# dustmap_lora.net
KiCad netlist of a schematic drawn in EAGLE
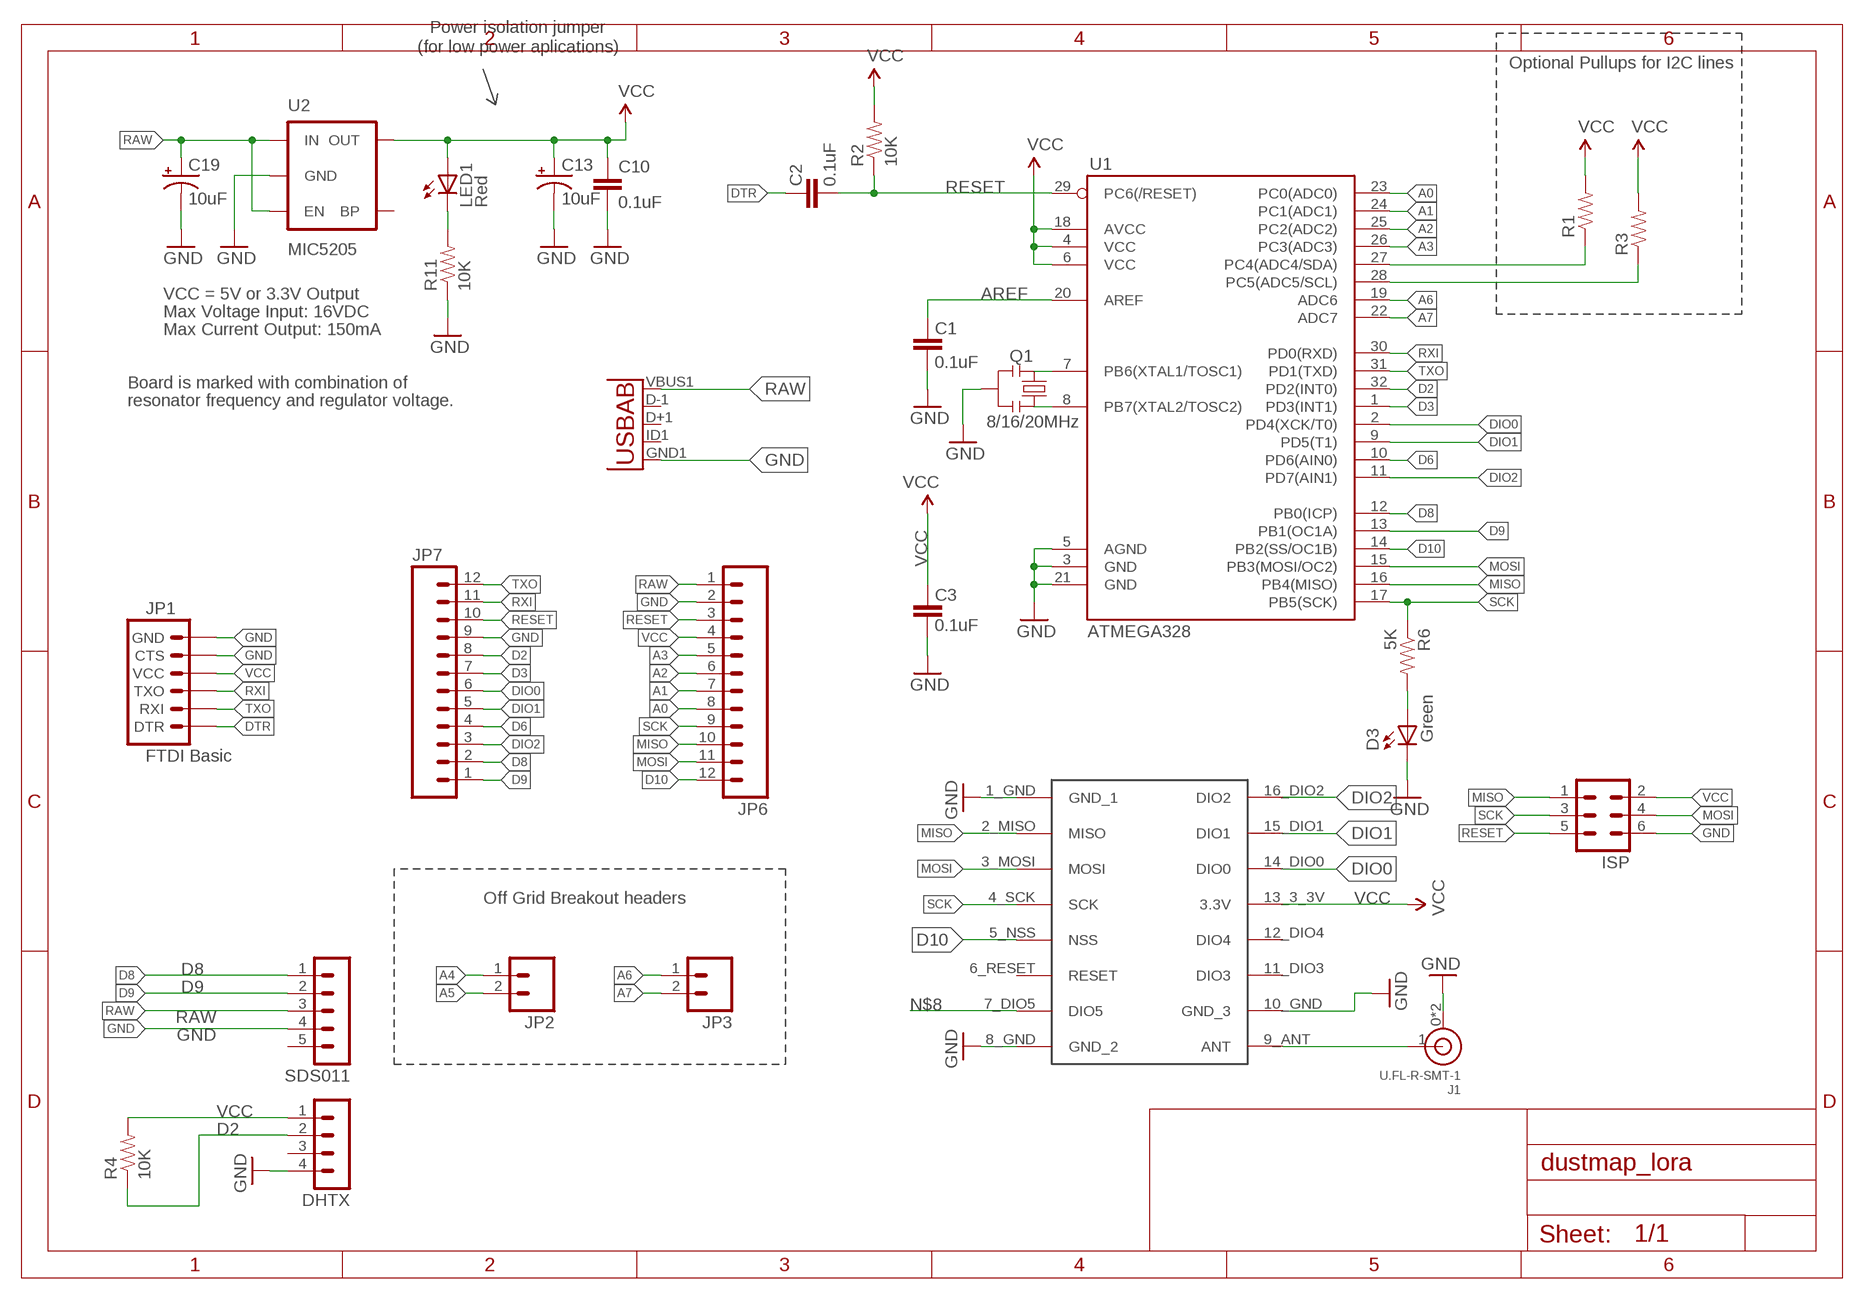
[diagram p0: schematic, sheet 1]

(export (version "E")
  (design (tool "Eeschema 10.0.6"))
  (components
    (comp (ref "C1")
      (value "0.1uF")
      (footprint "eagle-import:0603-CAP")
      (libsource (lib "eagle-import") (part "CAP0603-CAP"))
    )
    (comp (ref "C2")
      (value "0.1uF")
      (footprint "eagle-import:0603-CAP")
      (libsource (lib "eagle-import") (part "CAP0603-CAP"))
    )
    (comp (ref "C3")
      (value "0.1uF")
      (footprint "eagle-import:0603-CAP")
      (libsource (lib "eagle-import") (part "CAP0603-CAP"))
    )
    (comp (ref "C10")
      (value "0.1uF")
      (footprint "eagle-import:0603-CAP")
      (libsource (lib "eagle-import") (part "CAP0603-CAP"))
    )
    (comp (ref "C13")
      (value "10uF")
      (footprint "eagle-import:EIA3216")
      (libsource (lib "eagle-import") (part "CAP_POL1206"))
    )
    (comp (ref "C19")
      (value "10uF")
      (footprint "eagle-import:EIA3216")
      (libsource (lib "eagle-import") (part "CAP_POL1206"))
    )
    (comp (ref "D3")
      (value "Green")
      (footprint "eagle-import:0603-LED-ALT1")
      (libsource (lib "eagle-import") (part "LED"))
    )
    (comp (ref "DHTX")
      (value "MA04-1")
      (footprint "eagle-import:MA04-1")
      (libsource (lib "eagle-import") (part "MA04-1"))
    )
    (comp (ref "ISP")
      (value "MA03-2")
      (footprint "eagle-import:MA03-2")
      (libsource (lib "eagle-import") (part "MA03-2"))
    )
    (comp (ref "J1")
      (value "U.FL-R-SMT-1")
      (footprint "eagle-import:U.FL")
      (libsource (lib "eagle-import") (part "U.FL-R-SMT-1"))
    )
    (comp (ref "JP1")
      (value "FTDI Basic")
      (footprint "eagle-import:1X06")
      (libsource (lib "eagle-import") (part "ARDUINO_SERIAL_PROGRAMPTH"))
    )
    (comp (ref "JP2")
      (value "M02PTH")
      (footprint "eagle-import:1X02")
      (libsource (lib "eagle-import") (part "M02PTH"))
    )
    (comp (ref "JP3")
      (value "M02PTH")
      (footprint "eagle-import:1X02")
      (libsource (lib "eagle-import") (part "M02PTH"))
    )
    (comp (ref "JP6")
      (value "M12PTH")
      (footprint "eagle-import:1X12")
      (libsource (lib "eagle-import") (part "M12PTH"))
    )
    (comp (ref "JP7")
      (value "M12PTH")
      (footprint "eagle-import:1X12")
      (libsource (lib "eagle-import") (part "M12PTH"))
    )
    (comp (ref "LED1")
      (value "Red")
      (footprint "eagle-import:0603-LED-ALT1")
      (libsource (lib "eagle-import") (part "LED"))
    )
    (comp (ref "Q1")
      (value "8/16/20MHz")
      (footprint "eagle-import:RESONATOR-SMD-1_1")
      (libsource (lib "eagle-import") (part "RESONATOR1{colon}1"))
    )
    (comp (ref "R1")
      (value "RESISTOR0603-RES")
      (footprint "eagle-import:0603-RES")
      (libsource (lib "eagle-import") (part "RESISTOR0603-RES"))
    )
    (comp (ref "R2")
      (value "10K")
      (footprint "eagle-import:0603-RES")
      (libsource (lib "eagle-import") (part "RESISTOR0603-RES"))
    )
    (comp (ref "R3")
      (value "RESISTOR0603-RES")
      (footprint "eagle-import:0603-RES")
      (libsource (lib "eagle-import") (part "RESISTOR0603-RES"))
    )
    (comp (ref "R4")
      (value "10K")
      (footprint "eagle-import:0603-RES")
      (libsource (lib "eagle-import") (part "RESISTOR0603-RES"))
    )
    (comp (ref "R6")
      (value "5K")
      (footprint "eagle-import:0603-RES")
      (libsource (lib "eagle-import") (part "RESISTOR0603-RES"))
    )
    (comp (ref "R11")
      (value "10K")
      (footprint "eagle-import:0603-RES")
      (libsource (lib "eagle-import") (part "RESISTOR0603-RES"))
    )
    (comp (ref "SDS011")
      (value "MA05-1")
      (footprint "eagle-import:MA05-1")
      (libsource (lib "eagle-import") (part "MA05-1"))
    )
    (comp (ref "U$1")
      (value "RF96")
      (footprint "eagle-import:SMD")
      (libsource (lib "eagle-import") (part "RF96"))
    )
    (comp (ref "U1")
      (value "ATMEGA328")
      (footprint "eagle-import:TQFP32-08")
      (libsource (lib "eagle-import") (part "ATMEGA168"))
    )
    (comp (ref "U2")
      (value "MIC5205")
      (footprint "eagle-import:SOT23-5")
      (libsource (lib "eagle-import") (part "V_REG_LDOSMD"))
    )
    (comp (ref "U3")
      (value "USB\"\"")
      (footprint "eagle-import:USB-MICRO-SMD")
      (libsource (lib "eagle-import") (part "USB{dblquote}{dblquote}"))
    )
  )
  (nets
    (net (code "1") (name "/AREF") (class "Default")
      (node (ref "C1") (pin "2") (pinfunction "2_2") (pintype "passive"))
      (node (ref "U1") (pin "20") (pinfunction "AREF_20") (pintype "bidirectional"))
    )
    (net (code "2") (name "/N$8") (class "Default")
      (node (ref "U$1") (pin "7_DIO5") (pinfunction "DIO5_7_DIO5") (pintype "bidirectional"))
    )
    (net (code "3") (name "A0") (class "Default")
      (node (ref "JP6") (pin "8") (pinfunction "8_8") (pintype "passive"))
      (node (ref "U1") (pin "23") (pinfunction "PC0(ADC0)_23") (pintype "bidirectional"))
    )
    (net (code "4") (name "A1") (class "Default")
      (node (ref "JP6") (pin "7") (pinfunction "7_7") (pintype "passive"))
      (node (ref "U1") (pin "24") (pinfunction "PC1(ADC1)_24") (pintype "bidirectional"))
    )
    (net (code "5") (name "A2") (class "Default")
      (node (ref "JP6") (pin "6") (pinfunction "6_6") (pintype "passive"))
      (node (ref "U1") (pin "25") (pinfunction "PC2(ADC2)_25") (pintype "bidirectional"))
    )
    (net (code "6") (name "A3") (class "Default")
      (node (ref "JP6") (pin "5") (pinfunction "5_5") (pintype "passive"))
      (node (ref "U1") (pin "26") (pinfunction "PC3(ADC3)_26") (pintype "bidirectional"))
    )
    (net (code "7") (name "A4") (class "Default")
      (node (ref "JP2") (pin "1") (pinfunction "1_1") (pintype "passive"))
      (node (ref "R1") (pin "1") (pinfunction "1_1") (pintype "passive"))
      (node (ref "U1") (pin "27") (pinfunction "PC4(ADC4/SDA)_27") (pintype "bidirectional"))
    )
    (net (code "8") (name "A5") (class "Default")
      (node (ref "JP2") (pin "2") (pinfunction "2_2") (pintype "passive"))
      (node (ref "R3") (pin "1") (pinfunction "1_1") (pintype "passive"))
      (node (ref "U1") (pin "28") (pinfunction "PC5(ADC5/SCL)_28") (pintype "bidirectional"))
    )
    (net (code "9") (name "A6") (class "Default")
      (node (ref "JP3") (pin "1") (pinfunction "1_1") (pintype "passive"))
      (node (ref "U1") (pin "19") (pinfunction "ADC6_19") (pintype "bidirectional"))
    )
    (net (code "10") (name "A7") (class "Default")
      (node (ref "JP3") (pin "2") (pinfunction "2_2") (pintype "passive"))
      (node (ref "U1") (pin "22") (pinfunction "ADC7_22") (pintype "bidirectional"))
    )
    (net (code "11") (name "D2") (class "Default")
      (node (ref "DHTX") (pin "2") (pinfunction "2_2") (pintype "passive"))
      (node (ref "JP7") (pin "8") (pinfunction "8_8") (pintype "passive"))
      (node (ref "R4") (pin "1") (pinfunction "1_1") (pintype "passive"))
      (node (ref "U1") (pin "32") (pinfunction "PD2(INT0)_32") (pintype "bidirectional"))
    )
    (net (code "12") (name "D3") (class "Default")
      (node (ref "JP7") (pin "7") (pinfunction "7_7") (pintype "passive"))
      (node (ref "U1") (pin "1") (pinfunction "PD3(INT1)_1") (pintype "bidirectional"))
    )
    (net (code "13") (name "D6") (class "Default")
      (node (ref "JP7") (pin "4") (pinfunction "4_4") (pintype "passive"))
      (node (ref "U1") (pin "10") (pinfunction "PD6(AIN0)_10") (pintype "bidirectional"))
    )
    (net (code "14") (name "D8") (class "Default")
      (node (ref "JP7") (pin "2") (pinfunction "2_2") (pintype "passive"))
      (node (ref "SDS011") (pin "1") (pinfunction "1_1") (pintype "passive"))
      (node (ref "U1") (pin "12") (pinfunction "PB0(ICP)_12") (pintype "bidirectional"))
    )
    (net (code "15") (name "D9") (class "Default")
      (node (ref "JP7") (pin "1") (pinfunction "1_1") (pintype "passive"))
      (node (ref "SDS011") (pin "2") (pinfunction "2_2") (pintype "passive"))
      (node (ref "U1") (pin "13") (pinfunction "PB1(OC1A)_13") (pintype "bidirectional"))
    )
    (net (code "16") (name "D10") (class "Default")
      (node (ref "JP6") (pin "12") (pinfunction "12_12") (pintype "passive"))
      (node (ref "U$1") (pin "5_NSS") (pinfunction "NSS_5_NSS") (pintype "bidirectional"))
      (node (ref "U1") (pin "14") (pinfunction "PB2(SS/OC1B)_14") (pintype "bidirectional"))
    )
    (net (code "17") (name "DIO0") (class "Default")
      (node (ref "JP7") (pin "6") (pinfunction "6_6") (pintype "passive"))
      (node (ref "U$1") (pin "14_DIO0") (pinfunction "DIO0_14_DIO0") (pintype "bidirectional"))
      (node (ref "U1") (pin "2") (pinfunction "PD4(XCK/T0)_2") (pintype "bidirectional"))
    )
    (net (code "18") (name "DIO1") (class "Default")
      (node (ref "JP7") (pin "5") (pinfunction "5_5") (pintype "passive"))
      (node (ref "U$1") (pin "15_DIO1") (pinfunction "DIO1_15_DIO1") (pintype "bidirectional"))
      (node (ref "U1") (pin "9") (pinfunction "PD5(T1)_9") (pintype "bidirectional"))
    )
    (net (code "19") (name "DIO2") (class "Default")
      (node (ref "JP7") (pin "3") (pinfunction "3_3") (pintype "passive"))
      (node (ref "U$1") (pin "16_DIO2") (pinfunction "DIO2_16_DIO2") (pintype "bidirectional"))
      (node (ref "U1") (pin "11") (pinfunction "PD7(AIN1)_11") (pintype "bidirectional"))
    )
    (net (code "20") (name "DTR") (class "Default")
      (node (ref "C2") (pin "2") (pinfunction "2_2") (pintype "passive"))
      (node (ref "JP1") (pin "1") (pinfunction "DTR_1") (pintype "passive"))
    )
    (net (code "21") (name "GND") (class "Default")
      (node (ref "C1") (pin "1") (pinfunction "1_1") (pintype "passive"))
      (node (ref "C10") (pin "2") (pinfunction "2_2") (pintype "passive"))
      (node (ref "C13") (pin "C") (pinfunction "-_C") (pintype "passive"))
      (node (ref "C19") (pin "C") (pinfunction "-_C") (pintype "passive"))
      (node (ref "C3") (pin "1") (pinfunction "1_1") (pintype "passive"))
      (node (ref "D3") (pin "C") (pinfunction "C_C") (pintype "passive"))
      (node (ref "DHTX") (pin "4") (pinfunction "4_4") (pintype "passive"))
      (node (ref "ISP") (pin "6") (pinfunction "6_6") (pintype "passive"))
      (node (ref "J1") (pin "0") (pinfunction "GND_0") (pintype "passive"))
      (node (ref "J1") (pin "2") (pinfunction "GND_2") (pintype "passive"))
      (node (ref "JP1") (pin "5") (pinfunction "CTS_5") (pintype "passive"))
      (node (ref "JP1") (pin "6") (pinfunction "GND_6") (pintype "passive"))
      (node (ref "JP6") (pin "2") (pinfunction "2_2") (pintype "passive"))
      (node (ref "JP7") (pin "9") (pinfunction "9_9") (pintype "passive"))
      (node (ref "Q1") (pin "2") (pinfunction "2_2") (pintype "passive"))
      (node (ref "R11") (pin "1") (pinfunction "1_1") (pintype "passive"))
      (node (ref "SDS011") (pin "4") (pinfunction "4_4") (pintype "passive"))
      (node (ref "U$1") (pin "10_GND") (pinfunction "GND_3_10_GND") (pintype "bidirectional"))
      (node (ref "U$1") (pin "1_GND") (pinfunction "GND_1_1_GND") (pintype "bidirectional"))
      (node (ref "U$1") (pin "8_GND") (pinfunction "GND_2_8_GND") (pintype "bidirectional"))
      (node (ref "U1") (pin "21") (pinfunction "GND_21") (pintype "bidirectional"))
      (node (ref "U1") (pin "3") (pinfunction "GND_3") (pintype "bidirectional"))
      (node (ref "U1") (pin "5") (pinfunction "AGND_5") (pintype "bidirectional"))
      (node (ref "U2") (pin "2") (pinfunction "GND_2") (pintype "input"))
      (node (ref "U3") (pin "GND1") (pinfunction "GND_GND1") (pintype "bidirectional"))
    )
    (net (code "22") (name "MISO") (class "Default")
      (node (ref "ISP") (pin "1") (pinfunction "1_1") (pintype "passive"))
      (node (ref "JP6") (pin "10") (pinfunction "10_10") (pintype "passive"))
      (node (ref "U$1") (pin "2_MISO") (pinfunction "MISO_2_MISO") (pintype "bidirectional"))
      (node (ref "U1") (pin "16") (pinfunction "PB4(MISO)_16") (pintype "bidirectional"))
    )
    (net (code "23") (name "MOSI") (class "Default")
      (node (ref "ISP") (pin "4") (pinfunction "4_4") (pintype "passive"))
      (node (ref "JP6") (pin "11") (pinfunction "11_11") (pintype "passive"))
      (node (ref "U$1") (pin "3_MOSI") (pinfunction "MOSI_3_MOSI") (pintype "bidirectional"))
      (node (ref "U1") (pin "15") (pinfunction "PB3(MOSI/OC2)_15") (pintype "bidirectional"))
    )
    (net (code "24") (name "Net-(D3-PadA)") (class "Default")
      (node (ref "D3") (pin "A") (pinfunction "A_A") (pintype "passive"))
      (node (ref "R6") (pin "2") (pinfunction "2_2") (pintype "passive"))
    )
    (net (code "25") (name "Net-(J1-SIG)") (class "Default")
      (node (ref "J1") (pin "1") (pinfunction "SIG_1") (pintype "passive"))
      (node (ref "U$1") (pin "9_ANT") (pinfunction "ANT_9_ANT") (pintype "bidirectional"))
    )
    (net (code "26") (name "Net-(LED1-PadC)") (class "Default")
      (node (ref "LED1") (pin "C") (pinfunction "C_C") (pintype "passive"))
      (node (ref "R11") (pin "2") (pinfunction "2_2") (pintype "passive"))
    )
    (net (code "27") (name "Net-(U1-PB6(XTAL1{slash}TOSC1))") (class "Default")
      (node (ref "Q1") (pin "1") (pinfunction "1_1") (pintype "passive"))
      (node (ref "U1") (pin "7") (pinfunction "PB6(XTAL1/TOSC1)_7") (pintype "bidirectional"))
    )
    (net (code "28") (name "Net-(U1-PB7(XTAL2{slash}TOSC2))") (class "Default")
      (node (ref "Q1") (pin "3") (pinfunction "3_3") (pintype "passive"))
      (node (ref "U1") (pin "8") (pinfunction "PB7(XTAL2/TOSC2)_8") (pintype "bidirectional"))
    )
    (net (code "29") (name "RAW") (class "Default")
      (node (ref "C19") (pin "A") (pinfunction "+_A") (pintype "passive"))
      (node (ref "JP6") (pin "1") (pinfunction "1_1") (pintype "passive"))
      (node (ref "SDS011") (pin "3") (pinfunction "3_3") (pintype "passive"))
      (node (ref "U2") (pin "1") (pinfunction "IN_1") (pintype "input"))
      (node (ref "U2") (pin "3") (pinfunction "EN_3") (pintype "input"))
      (node (ref "U3") (pin "VBUS1") (pinfunction "VBUS_VBUS1") (pintype "bidirectional"))
    )
    (net (code "30") (name "RESET") (class "Default")
      (node (ref "C2") (pin "1") (pinfunction "1_1") (pintype "passive"))
      (node (ref "ISP") (pin "5") (pinfunction "5_5") (pintype "passive"))
      (node (ref "JP6") (pin "3") (pinfunction "3_3") (pintype "passive"))
      (node (ref "JP7") (pin "10") (pinfunction "10_10") (pintype "passive"))
      (node (ref "R2") (pin "1") (pinfunction "1_1") (pintype "passive"))
      (node (ref "U1") (pin "29") (pinfunction "PC6(/RESET)_29") (pintype "bidirectional"))
    )
    (net (code "31") (name "RXI") (class "Default")
      (node (ref "JP1") (pin "3") (pinfunction "TXO_3") (pintype "passive"))
      (node (ref "JP7") (pin "11") (pinfunction "11_11") (pintype "passive"))
      (node (ref "U1") (pin "30") (pinfunction "PD0(RXD)_30") (pintype "bidirectional"))
    )
    (net (code "32") (name "SCK") (class "Default")
      (node (ref "ISP") (pin "3") (pinfunction "3_3") (pintype "passive"))
      (node (ref "JP6") (pin "9") (pinfunction "9_9") (pintype "passive"))
      (node (ref "R6") (pin "1") (pinfunction "1_1") (pintype "passive"))
      (node (ref "U$1") (pin "4_SCK") (pinfunction "SCK_4_SCK") (pintype "bidirectional"))
      (node (ref "U1") (pin "17") (pinfunction "PB5(SCK)_17") (pintype "bidirectional"))
    )
    (net (code "33") (name "TXO") (class "Default")
      (node (ref "JP1") (pin "2") (pinfunction "RXI_2") (pintype "passive"))
      (node (ref "JP7") (pin "12") (pinfunction "12_12") (pintype "passive"))
      (node (ref "U1") (pin "31") (pinfunction "PD1(TXD)_31") (pintype "bidirectional"))
    )
    (net (code "34") (name "VCC") (class "Default")
      (node (ref "C10") (pin "1") (pinfunction "1_1") (pintype "passive"))
      (node (ref "C13") (pin "A") (pinfunction "+_A") (pintype "passive"))
      (node (ref "C3") (pin "2") (pinfunction "2_2") (pintype "passive"))
      (node (ref "DHTX") (pin "1") (pinfunction "1_1") (pintype "passive"))
      (node (ref "ISP") (pin "2") (pinfunction "2_2") (pintype "passive"))
      (node (ref "JP1") (pin "4") (pinfunction "VCC_4") (pintype "passive"))
      (node (ref "JP6") (pin "4") (pinfunction "4_4") (pintype "passive"))
      (node (ref "LED1") (pin "A") (pinfunction "A_A") (pintype "passive"))
      (node (ref "R1") (pin "2") (pinfunction "2_2") (pintype "passive"))
      (node (ref "R2") (pin "2") (pinfunction "2_2") (pintype "passive"))
      (node (ref "R3") (pin "2") (pinfunction "2_2") (pintype "passive"))
      (node (ref "R4") (pin "2") (pinfunction "2_2") (pintype "passive"))
      (node (ref "U$1") (pin "13_3_3V") (pinfunction "3.3V_13_3_3V") (pintype "bidirectional"))
      (node (ref "U1") (pin "18") (pinfunction "AVCC_18") (pintype "bidirectional"))
      (node (ref "U1") (pin "4") (pinfunction "VCC_4") (pintype "bidirectional"))
      (node (ref "U1") (pin "6") (pinfunction "VCC_6") (pintype "bidirectional"))
      (node (ref "U2") (pin "5") (pinfunction "OUT_5") (pintype "passive"))
    )
    (net (code "35") (name "unconnected-(DHTX-Pad3)") (class "Default")
      (node (ref "DHTX") (pin "3") (pinfunction "3_3") (pintype "passive"))
    )
    (net (code "36") (name "unconnected-(SDS011-Pad5)") (class "Default")
      (node (ref "SDS011") (pin "5") (pinfunction "5_5") (pintype "passive"))
    )
    (net (code "37") (name "unconnected-(U$1-DIO3-Pad11_DIO3)") (class "Default")
      (node (ref "U$1") (pin "11_DIO3") (pinfunction "DIO3_11_DIO3") (pintype "bidirectional"))
    )
    (net (code "38") (name "unconnected-(U$1-DIO4-Pad12_DIO4)") (class "Default")
      (node (ref "U$1") (pin "12_DIO4") (pinfunction "DIO4_12_DIO4") (pintype "bidirectional"))
    )
    (net (code "39") (name "unconnected-(U$1-RESET-Pad6_RESET)") (class "Default")
      (node (ref "U$1") (pin "6_RESET") (pinfunction "RESET_6_RESET") (pintype "bidirectional"))
    )
    (net (code "40") (name "unconnected-(U2-BP-Pad4)") (class "Default")
      (node (ref "U2") (pin "4") (pinfunction "BP_4") (pintype "input"))
    )
    (net (code "41") (name "unconnected-(U3-D+-PadD+1)") (class "Default")
      (node (ref "U3") (pin "D+1") (pinfunction "D+_D+1") (pintype "bidirectional"))
    )
    (net (code "42") (name "unconnected-(U3-D--PadD-1)") (class "Default")
      (node (ref "U3") (pin "D-1") (pinfunction "D-_D-1") (pintype "bidirectional"))
    )
    (net (code "43") (name "unconnected-(U3-USBID-PadID1)") (class "Default")
      (node (ref "U3") (pin "ID1") (pinfunction "USBID_ID1") (pintype "bidirectional"))
    )
  )
)
